# ADJ_REG.net
KiCad netlist of a schematic drawn in Altium Designer
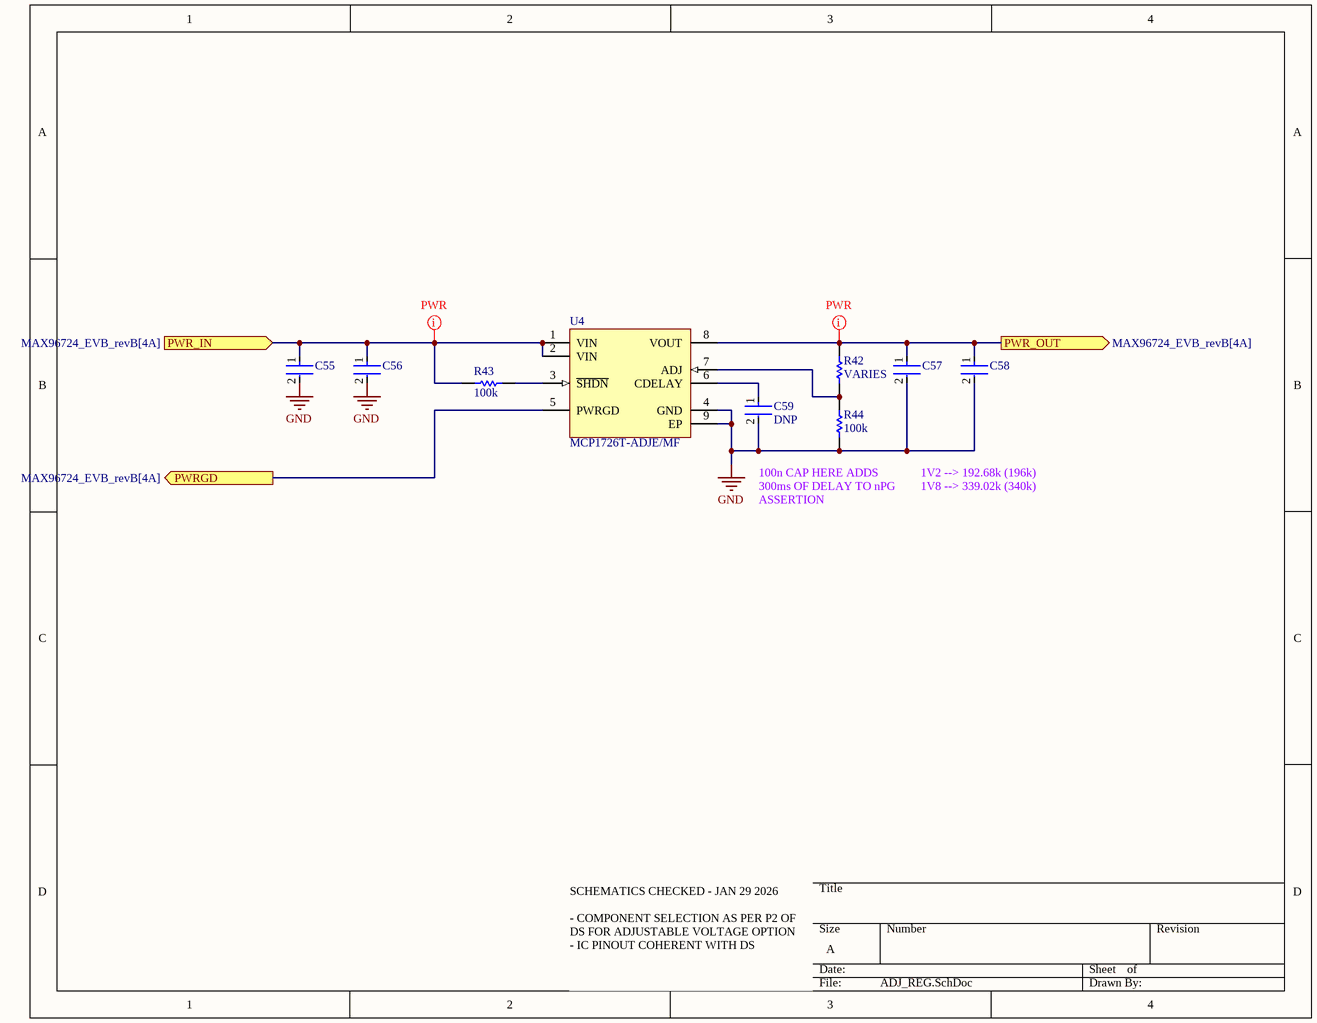
[diagram p0: ADJ_REG.SchDoc]

(export (version "E")
  (design (tool "Eeschema 10.0.6"))
  (components
    (comp (ref "C55")
      (value "C0805C475J4RACAUTO")
      (footprint "FP-C0805C475J4RACAUTO-MFG")
      (description "C0805C475J4RACAUTO Cap Ceramic 4.7uF 16V X7R 5% Pad SMD 0805 125C Automotive T/R")
      (fields (field (name "TOLERANCE") "5%"))
      (libsource (lib "Altium Content Vault") (part "b4654b650e69147ec39a6b967a45e02"))
    )
    (comp (ref "C56")
      (value "DNP")
      (footprint "FP-C0805C475J4RACAUTO-MFG")
      (description "C0805C475J4RACAUTO Cap Ceramic 4.7uF 16V X7R 5% Pad SMD 0805 125C Automotive T/R")
      (fields (field (name "TOLERANCE") "5%"))
      (libsource (lib "Altium Content Vault") (part "b4654b650e69147ec39a6b967a45e02"))
    )
    (comp (ref "C57")
      (value "HMK325B7105KN-T")
      (footprint "FP-1210-L_3_2_0_3-W_2_5_0-IPC_B")
      (description "None")
      (fields (field (name "TOLERANCE") "10%") (field (name "VOLTAGE") "100V"))
      (libsource (lib "Altium Content Vault") (part "02cd4be3c70576c341d710602a673aa"))
    )
    (comp (ref "C58")
      (value "DNP")
      (footprint "FP-1210-L_3_2_0_3-W_2_5_0-IPC_B")
      (description "None")
      (fields (field (name "TOLERANCE") "10%") (field (name "VOLTAGE") "100V"))
      (libsource (lib "Altium Content Vault") (part "02cd4be3c70576c341d710602a673aa"))
    )
    (comp (ref "C59")
      (value "DNP")
      (footprint "FP-0402-L_1_0_0_05-W_0_5-IPC_A")
      (description "LARGE PADS, 0402 CAP, CHANGE COMMENT TO MATCH REAL P/N")
      (libsource (lib "Space Concordia") (part "b4654b650e69147ec39a6b967a45e02"))
    )
    (comp (ref "R42")
      (value "VARIES")
      (footprint "R0603B")
      (description "Resistor")
      (libsource (lib "Space Concordia") (part "Resistor"))
    )
    (comp (ref "R43")
      (value "100k")
      (footprint "R0603B")
      (description "Resistor")
      (libsource (lib "Space Concordia") (part "Resistor"))
    )
    (comp (ref "R44")
      (value "100k")
      (footprint "R0603B")
      (description "Resistor")
      (libsource (lib "Space Concordia") (part "Resistor"))
    )
    (comp (ref "U4")
      (value "MCP1726T-ADJE/MF")
      (footprint "DFN-MF8")
      (libsource (lib "Altium Content Vault") (part "PM-LINEREG-MCP1726-IL9A"))
    )
  )
  (nets
    (net (code "1") (name "/PWRGD") (class "Default")
      (node (ref "U4") (pin "5") (pinfunction "PWRGD_5") (pintype "power_in"))
    )
    (net (code "2") (name "/PWR_IN") (class "Default")
      (node (ref "C55") (pin "1") (pinfunction "1_1") (pintype "passive"))
      (node (ref "C56") (pin "1") (pinfunction "1_1") (pintype "passive"))
      (node (ref "R43") (pin "1") (pinfunction "1_1") (pintype "passive"))
      (node (ref "U4") (pin "1") (pinfunction "VIN_1") (pintype "power_in"))
      (node (ref "U4") (pin "2") (pinfunction "VIN_2") (pintype "power_in"))
    )
    (net (code "3") (name "/PWR_OUT") (class "Default")
      (node (ref "C57") (pin "1") (pinfunction "1_1") (pintype "passive"))
      (node (ref "C58") (pin "1") (pinfunction "1_1") (pintype "passive"))
      (node (ref "R42") (pin "2") (pinfunction "2_2") (pintype "passive"))
      (node (ref "U4") (pin "8") (pinfunction "VOUT_8") (pintype "power_in"))
    )
    (net (code "4") (name "GND") (class "Default")
      (node (ref "C55") (pin "2") (pinfunction "2_2") (pintype "passive"))
      (node (ref "C56") (pin "2") (pinfunction "2_2") (pintype "passive"))
      (node (ref "C57") (pin "2") (pinfunction "2_2") (pintype "passive"))
      (node (ref "C58") (pin "2") (pinfunction "2_2") (pintype "passive"))
      (node (ref "C59") (pin "2") (pinfunction "2_2") (pintype "passive"))
      (node (ref "R44") (pin "1") (pinfunction "1_1") (pintype "passive"))
      (node (ref "U4") (pin "4") (pinfunction "GND_4") (pintype "power_in"))
      (node (ref "U4") (pin "9") (pinfunction "EP_9") (pintype "power_in"))
    )
    (net (code "5") (name "Net-(U4-ADJ)") (class "Default")
      (node (ref "R42") (pin "1") (pinfunction "1_1") (pintype "passive"))
      (node (ref "R44") (pin "2") (pinfunction "2_2") (pintype "passive"))
      (node (ref "U4") (pin "7") (pinfunction "ADJ_7") (pintype "input"))
    )
    (net (code "6") (name "Net-(U4-CDELAY)") (class "Default")
      (node (ref "C59") (pin "1") (pinfunction "1_1") (pintype "passive"))
      (node (ref "U4") (pin "6") (pinfunction "CDELAY_6") (pintype "passive"))
    )
    (net (code "7") (name "Net-(U4-~{SHDN})") (class "Default")
      (node (ref "R43") (pin "2") (pinfunction "2_2") (pintype "passive"))
      (node (ref "U4") (pin "3") (pinfunction "~{SHDN}_3") (pintype "input"))
    )
  )
)
